# BrushTimer.net
KiCad netlist of a schematic drawn in EAGLE
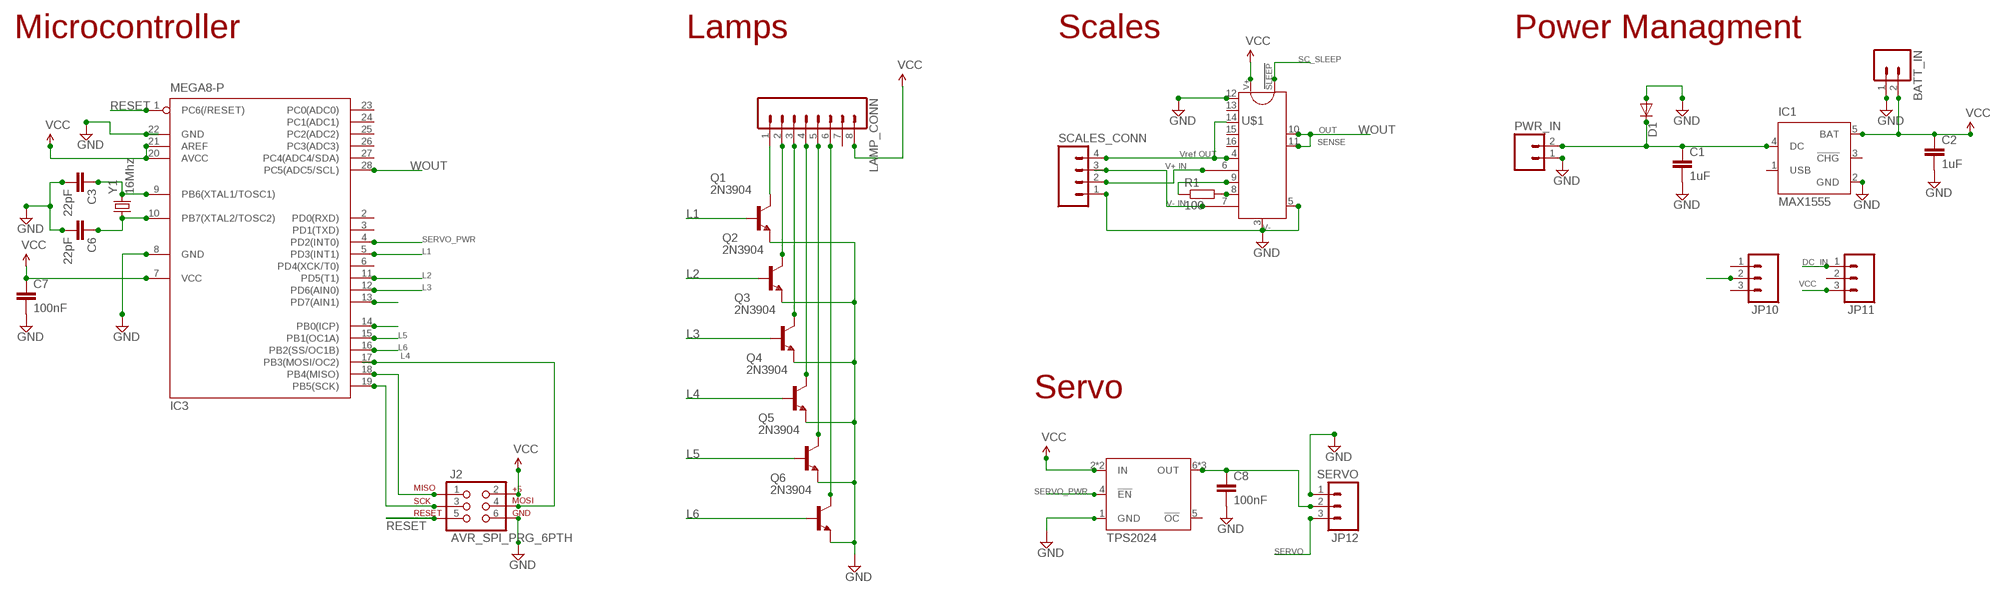
[diagram p0: schematic, sheet 1]

(export (version "E")
  (design (tool "Eeschema 10.0.6"))
  (components
    (comp (ref "BATT_IN")
      (value "M02PTH")
      (footprint "eagle-import:1X02")
      (libsource (lib "eagle-import") (part "M02PTH"))
    )
    (comp (ref "C1")
      (value "1uF")
      (footprint "eagle-import:AXIAL-5MM")
      (libsource (lib "eagle-import") (part "CAP_"))
    )
    (comp (ref "C2")
      (value "1uF")
      (footprint "eagle-import:AXIAL-5MM")
      (libsource (lib "eagle-import") (part "CAP_"))
    )
    (comp (ref "C3")
      (value "22pF")
      (footprint "eagle-import:C2.5-2")
      (libsource (lib "eagle-import") (part "C2.5/2"))
    )
    (comp (ref "C6")
      (value "22pF")
      (footprint "eagle-import:C2.5-2")
      (libsource (lib "eagle-import") (part "C2.5/2"))
    )
    (comp (ref "C7")
      (value "100nF")
      (footprint "eagle-import:C5B3.5")
      (libsource (lib "eagle-import") (part "C5/3.5"))
    )
    (comp (ref "C8")
      (value "100nF")
      (footprint "eagle-import:C5B3.5")
      (libsource (lib "eagle-import") (part "C5/3.5"))
    )
    (comp (ref "D1")
      (value "DIODE-D-2.5")
      (footprint "eagle-import:D-2.5")
      (libsource (lib "eagle-import") (part "DIODE-D-2.5"))
    )
    (comp (ref "IC1")
      (value "MAX1555")
      (footprint "eagle-import:SOT23-5L")
      (fields (field (name "MF") "MAXIM") (field (name "MPN") "MAX1555EZK+T"))
      (libsource (lib "eagle-import") (part "MAX1555"))
    )
    (comp (ref "IC3")
      (value "MEGA8-P")
      (footprint "eagle-import:DIL28-3")
      (libsource (lib "eagle-import") (part "MEGA8-P"))
    )
    (comp (ref "J2")
      (value "AVR_SPI_PRG_6PTH")
      (footprint "eagle-import:2X3")
      (libsource (lib "eagle-import") (part "AVR_SPI_PRG_6PTH"))
    )
    (comp (ref "JP10")
      (value "M03PTH")
      (footprint "eagle-import:1X03")
      (libsource (lib "eagle-import") (part "M03PTH"))
    )
    (comp (ref "JP11")
      (value "M03PTH")
      (footprint "eagle-import:1X03")
      (libsource (lib "eagle-import") (part "M03PTH"))
    )
    (comp (ref "JP12")
      (value "SERVO")
      (footprint "eagle-import:1X03")
      (libsource (lib "eagle-import") (part "M03PTH"))
    )
    (comp (ref "LAMP_CONN")
      (value "M081X08")
      (footprint "eagle-import:1X08")
      (libsource (lib "eagle-import") (part "M081X08"))
    )
    (comp (ref "PWR_IN")
      (value "M02PTH")
      (footprint "eagle-import:1X02")
      (libsource (lib "eagle-import") (part "M02PTH"))
    )
    (comp (ref "Q1")
      (value "2N3904")
      (footprint "eagle-import:TO92")
      (libsource (lib "eagle-import") (part "2N3904"))
    )
    (comp (ref "Q2")
      (value "2N3904")
      (footprint "eagle-import:TO92")
      (libsource (lib "eagle-import") (part "2N3904"))
    )
    (comp (ref "Q3")
      (value "2N3904")
      (footprint "eagle-import:TO92")
      (libsource (lib "eagle-import") (part "2N3904"))
    )
    (comp (ref "Q4")
      (value "2N3904")
      (footprint "eagle-import:TO92")
      (libsource (lib "eagle-import") (part "2N3904"))
    )
    (comp (ref "Q5")
      (value "2N3904")
      (footprint "eagle-import:TO92")
      (libsource (lib "eagle-import") (part "2N3904"))
    )
    (comp (ref "Q6")
      (value "2N3904")
      (footprint "eagle-import:TO92")
      (libsource (lib "eagle-import") (part "2N3904"))
    )
    (comp (ref "R1")
      (value "100")
      (footprint "eagle-import:0207_5V")
      (libsource (lib "eagle-import") (part "R-EU_0207/5V"))
    )
    (comp (ref "SCALES_CONN")
      (value "M04PTH")
      (footprint "eagle-import:1X04")
      (libsource (lib "eagle-import") (part "M04PTH"))
    )
    (comp (ref "U$1")
      (value "INA125")
      (footprint "eagle-import:DIL16")
      (libsource (lib "eagle-import") (part "INA125"))
    )
    (comp (ref "U$2")
      (value "TPS2024")
      (footprint "eagle-import:DIL08-OPTO")
      (libsource (lib "eagle-import") (part "TPS2024"))
    )
    (comp (ref "Y1")
      (value "16Mhz")
      (footprint "eagle-import:HC49US")
      (libsource (lib "eagle-import") (part "CRYSTALHC49US"))
    )
  )
  (nets
    (net (code "1") (name "/DC_IN") (class "Default")
      (node (ref "C1") (pin "P$1") (pinfunction "1_P$1") (pintype "passive"))
      (node (ref "D1") (pin "C") (pinfunction "C_C") (pintype "passive"))
      (node (ref "IC1") (pin "4") (pinfunction "DC_4") (pintype "input"))
      (node (ref "JP11") (pin "1") (pinfunction "1_1") (pintype "passive"))
      (node (ref "PWR_IN") (pin "2") (pinfunction "2_2") (pintype "passive"))
    )
    (net (code "2") (name "/L1") (class "Default")
      (node (ref "IC3") (pin "5") (pinfunction "PD3(INT1)_5") (pintype "bidirectional"))
      (node (ref "Q1") (pin "2") (pinfunction "B_2") (pintype "passive"))
    )
    (net (code "3") (name "/L2") (class "Default")
      (node (ref "IC3") (pin "11") (pinfunction "PD5(T1)_11") (pintype "bidirectional"))
      (node (ref "Q2") (pin "2") (pinfunction "B_2") (pintype "passive"))
    )
    (net (code "4") (name "/L3") (class "Default")
      (node (ref "IC3") (pin "12") (pinfunction "PD6(AIN0)_12") (pintype "bidirectional"))
      (node (ref "Q3") (pin "2") (pinfunction "B_2") (pintype "passive"))
    )
    (net (code "5") (name "/L4") (class "Default")
      (node (ref "IC3") (pin "17") (pinfunction "PB3(MOSI/OC2)_17") (pintype "bidirectional"))
      (node (ref "J2") (pin "4") (pinfunction "4_4") (pintype "passive"))
      (node (ref "Q4") (pin "2") (pinfunction "B_2") (pintype "passive"))
    )
    (net (code "6") (name "/L5") (class "Default")
      (node (ref "IC3") (pin "15") (pinfunction "PB1(OC1A)_15") (pintype "bidirectional"))
      (node (ref "Q5") (pin "2") (pinfunction "B_2") (pintype "passive"))
    )
    (net (code "7") (name "/L6") (class "Default")
      (node (ref "IC3") (pin "16") (pinfunction "PB2(SS/OC1B)_16") (pintype "bidirectional"))
      (node (ref "Q6") (pin "2") (pinfunction "B_2") (pintype "passive"))
    )
    (net (code "8") (name "/RESET") (class "Default")
      (node (ref "IC3") (pin "1") (pinfunction "PC6(/RESET)_1") (pintype "bidirectional"))
      (node (ref "J2") (pin "5") (pinfunction "5_5") (pintype "passive"))
    )
    (net (code "9") (name "/SC_SLEEP") (class "Default")
      (node (ref "IC3") (pin "13") (pinfunction "PD7(AIN1)_13") (pintype "bidirectional"))
      (node (ref "U$1") (pin "2") (pinfunction "2_2") (pintype "power_in"))
    )
    (net (code "10") (name "/SERVO") (class "Default")
      (node (ref "IC3") (pin "14") (pinfunction "PB0(ICP)_14") (pintype "bidirectional"))
      (node (ref "JP12") (pin "3") (pinfunction "3_3") (pintype "passive"))
    )
    (net (code "11") (name "/SERVO_PWR") (class "Default")
      (node (ref "IC3") (pin "4") (pinfunction "PD2(INT0)_4") (pintype "bidirectional"))
      (node (ref "U$2") (pin "4") (pinfunction "~{EN}_4") (pintype "input"))
    )
    (net (code "12") (name "/WOUT") (class "Default")
      (node (ref "IC3") (pin "28") (pinfunction "PC5(ADC5/SCL)_28") (pintype "bidirectional"))
      (node (ref "U$1") (pin "10") (pinfunction "10_10") (pintype "output"))
      (node (ref "U$1") (pin "11") (pinfunction "11_11") (pintype "output"))
    )
    (net (code "13") (name "GND") (class "Default")
      (node (ref "BATT_IN") (pin "1") (pinfunction "1_1") (pintype "passive"))
      (node (ref "C1") (pin "P$2") (pinfunction "2_P$2") (pintype "passive"))
      (node (ref "C2") (pin "P$2") (pinfunction "2_P$2") (pintype "passive"))
      (node (ref "C3") (pin "2") (pinfunction "2_2") (pintype "passive"))
      (node (ref "C6") (pin "2") (pinfunction "2_2") (pintype "passive"))
      (node (ref "C7") (pin "2") (pinfunction "2_2") (pintype "passive"))
      (node (ref "C8") (pin "2") (pinfunction "2_2") (pintype "passive"))
      (node (ref "D1") (pin "A") (pinfunction "A_A") (pintype "passive"))
      (node (ref "IC1") (pin "2") (pinfunction "GND_2") (pintype "power_in"))
      (node (ref "IC3") (pin "22") (pinfunction "GND_22") (pintype "power_in"))
      (node (ref "IC3") (pin "8") (pinfunction "GND_8") (pintype "power_in"))
      (node (ref "J2") (pin "6") (pinfunction "6_6") (pintype "passive"))
      (node (ref "JP10") (pin "2") (pinfunction "2_2") (pintype "passive"))
      (node (ref "JP12") (pin "1") (pinfunction "1_1") (pintype "passive"))
      (node (ref "PWR_IN") (pin "1") (pinfunction "1_1") (pintype "passive"))
      (node (ref "Q1") (pin "3") (pinfunction "E_3") (pintype "passive"))
      (node (ref "Q2") (pin "3") (pinfunction "E_3") (pintype "passive"))
      (node (ref "Q3") (pin "3") (pinfunction "E_3") (pintype "passive"))
      (node (ref "Q4") (pin "3") (pinfunction "E_3") (pintype "passive"))
      (node (ref "Q5") (pin "3") (pinfunction "E_3") (pintype "passive"))
      (node (ref "Q6") (pin "3") (pinfunction "E_3") (pintype "passive"))
      (node (ref "SCALES_CONN") (pin "1") (pinfunction "1_1") (pintype "passive"))
      (node (ref "U$1") (pin "12") (pinfunction "12_12") (pintype "input"))
      (node (ref "U$1") (pin "3") (pinfunction "3_3") (pintype "passive"))
      (node (ref "U$1") (pin "5") (pinfunction "5_5") (pintype "passive"))
      (node (ref "U$2") (pin "1") (pinfunction "GND_1") (pintype "power_in"))
    )
    (net (code "14") (name "Net-(C8-Pad1)") (class "Default")
      (node (ref "C8") (pin "1") (pinfunction "1_1") (pintype "passive"))
      (node (ref "JP12") (pin "2") (pinfunction "2_2") (pintype "passive"))
      (node (ref "U$2") (pin "6") (pinfunction "OUT_6") (pintype "output"))
      (node (ref "U$2") (pin "7") (pinfunction "OUT_7") (pintype "output"))
      (node (ref "U$2") (pin "8") (pinfunction "OUT_8") (pintype "output"))
    )
    (net (code "15") (name "Net-(IC3-PB4(MISO))") (class "Default")
      (node (ref "IC3") (pin "18") (pinfunction "PB4(MISO)_18") (pintype "bidirectional"))
      (node (ref "J2") (pin "1") (pinfunction "1_1") (pintype "passive"))
    )
    (net (code "16") (name "Net-(IC3-PB5(SCK))") (class "Default")
      (node (ref "IC3") (pin "19") (pinfunction "PB5(SCK)_19") (pintype "bidirectional"))
      (node (ref "J2") (pin "3") (pinfunction "3_3") (pintype "passive"))
    )
    (net (code "17") (name "Net-(IC3-PB6(XTAL1{slash}TOSC1))") (class "Default")
      (node (ref "C3") (pin "1") (pinfunction "1_1") (pintype "passive"))
      (node (ref "IC3") (pin "9") (pinfunction "PB6(XTAL1/TOSC1)_9") (pintype "bidirectional"))
      (node (ref "Y1") (pin "2") (pinfunction "2_2") (pintype "passive"))
    )
    (net (code "18") (name "Net-(IC3-PB7(XTAL2{slash}TOSC2))") (class "Default")
      (node (ref "C6") (pin "1") (pinfunction "1_1") (pintype "passive"))
      (node (ref "IC3") (pin "10") (pinfunction "PB7(XTAL2/TOSC2)_10") (pintype "bidirectional"))
      (node (ref "Y1") (pin "1") (pinfunction "1_1") (pintype "passive"))
    )
    (net (code "19") (name "Net-(Q1-C)") (class "Default")
      (node (ref "LAMP_CONN") (pin "1") (pinfunction "1_1") (pintype "passive"))
      (node (ref "Q1") (pin "1") (pinfunction "C_1") (pintype "passive"))
    )
    (net (code "20") (name "Net-(Q2-C)") (class "Default")
      (node (ref "LAMP_CONN") (pin "2") (pinfunction "2_2") (pintype "passive"))
      (node (ref "Q2") (pin "1") (pinfunction "C_1") (pintype "passive"))
    )
    (net (code "21") (name "Net-(Q3-C)") (class "Default")
      (node (ref "LAMP_CONN") (pin "3") (pinfunction "3_3") (pintype "passive"))
      (node (ref "Q3") (pin "1") (pinfunction "C_1") (pintype "passive"))
    )
    (net (code "22") (name "Net-(Q4-C)") (class "Default")
      (node (ref "LAMP_CONN") (pin "4") (pinfunction "4_4") (pintype "passive"))
      (node (ref "Q4") (pin "1") (pinfunction "C_1") (pintype "passive"))
    )
    (net (code "23") (name "Net-(Q5-C)") (class "Default")
      (node (ref "LAMP_CONN") (pin "5") (pinfunction "5_5") (pintype "passive"))
      (node (ref "Q5") (pin "1") (pinfunction "C_1") (pintype "passive"))
    )
    (net (code "24") (name "Net-(Q6-C)") (class "Default")
      (node (ref "LAMP_CONN") (pin "6") (pinfunction "6_6") (pintype "passive"))
      (node (ref "Q6") (pin "1") (pinfunction "C_1") (pintype "passive"))
    )
    (net (code "25") (name "Net-(R1-Pad1)") (class "Default")
      (node (ref "R1") (pin "1") (pinfunction "1_1") (pintype "passive"))
      (node (ref "U$1") (pin "9") (pinfunction "9_9") (pintype "passive"))
    )
    (net (code "26") (name "Net-(R1-Pad2)") (class "Default")
      (node (ref "R1") (pin "2") (pinfunction "2_2") (pintype "passive"))
      (node (ref "U$1") (pin "8") (pinfunction "8_8") (pintype "passive"))
    )
    (net (code "27") (name "Net-(SCALES_CONN-Pad2)") (class "Default")
      (node (ref "SCALES_CONN") (pin "2") (pinfunction "2_2") (pintype "passive"))
      (node (ref "U$1") (pin "6") (pinfunction "6_6") (pintype "input"))
    )
    (net (code "28") (name "Net-(SCALES_CONN-Pad3)") (class "Default")
      (node (ref "SCALES_CONN") (pin "3") (pinfunction "3_3") (pintype "passive"))
      (node (ref "U$1") (pin "7") (pinfunction "7_7") (pintype "passive"))
    )
    (net (code "29") (name "Net-(SCALES_CONN-Pad4)") (class "Default")
      (node (ref "SCALES_CONN") (pin "4") (pinfunction "4_4") (pintype "passive"))
      (node (ref "U$1") (pin "14") (pinfunction "14_14") (pintype "input"))
      (node (ref "U$1") (pin "4") (pinfunction "4_4") (pintype "input"))
    )
    (net (code "30") (name "VCC") (class "Default")
      (node (ref "BATT_IN") (pin "2") (pinfunction "2_2") (pintype "passive"))
      (node (ref "C2") (pin "P$1") (pinfunction "1_P$1") (pintype "passive"))
      (node (ref "C7") (pin "1") (pinfunction "1_1") (pintype "passive"))
      (node (ref "IC1") (pin "5") (pinfunction "BAT_5") (pintype "passive"))
      (node (ref "IC3") (pin "20") (pinfunction "AVCC_20") (pintype "power_in"))
      (node (ref "IC3") (pin "21") (pinfunction "AREF_21") (pintype "passive"))
      (node (ref "IC3") (pin "7") (pinfunction "VCC_7") (pintype "power_in"))
      (node (ref "J2") (pin "2") (pinfunction "2_2") (pintype "passive"))
      (node (ref "JP11") (pin "3") (pinfunction "3_3") (pintype "passive"))
      (node (ref "LAMP_CONN") (pin "8") (pinfunction "8_8") (pintype "passive"))
      (node (ref "U$1") (pin "1") (pinfunction "1_1") (pintype "power_in"))
      (node (ref "U$2") (pin "2") (pinfunction "IN_2") (pintype "input"))
      (node (ref "U$2") (pin "3") (pinfunction "IN_3") (pintype "input"))
    )
    (net (code "31") (name "unconnected-(IC1-USB-Pad1)") (class "Default")
      (node (ref "IC1") (pin "1") (pinfunction "USB_1") (pintype "input"))
    )
    (net (code "32") (name "unconnected-(IC1-~{CHG}-Pad3)") (class "Default")
      (node (ref "IC1") (pin "3") (pinfunction "~{CHG}_3") (pintype "output"))
    )
    (net (code "33") (name "unconnected-(IC3-PC0(ADC0)-Pad23)") (class "Default")
      (node (ref "IC3") (pin "23") (pinfunction "PC0(ADC0)_23") (pintype "bidirectional"))
    )
    (net (code "34") (name "unconnected-(IC3-PC1(ADC1)-Pad24)") (class "Default")
      (node (ref "IC3") (pin "24") (pinfunction "PC1(ADC1)_24") (pintype "bidirectional"))
    )
    (net (code "35") (name "unconnected-(IC3-PC2(ADC2)-Pad25)") (class "Default")
      (node (ref "IC3") (pin "25") (pinfunction "PC2(ADC2)_25") (pintype "bidirectional"))
    )
    (net (code "36") (name "unconnected-(IC3-PC3(ADC3)-Pad26)") (class "Default")
      (node (ref "IC3") (pin "26") (pinfunction "PC3(ADC3)_26") (pintype "bidirectional"))
    )
    (net (code "37") (name "unconnected-(IC3-PC4(ADC4{slash}SDA)-Pad27)") (class "Default")
      (node (ref "IC3") (pin "27") (pinfunction "PC4(ADC4/SDA)_27") (pintype "bidirectional"))
    )
    (net (code "38") (name "unconnected-(IC3-PD0(RXD)-Pad2)") (class "Default")
      (node (ref "IC3") (pin "2") (pinfunction "PD0(RXD)_2") (pintype "bidirectional"))
    )
    (net (code "39") (name "unconnected-(IC3-PD1(TXD)-Pad3)") (class "Default")
      (node (ref "IC3") (pin "3") (pinfunction "PD1(TXD)_3") (pintype "bidirectional"))
    )
    (net (code "40") (name "unconnected-(IC3-PD4(XCK{slash}T0)-Pad6)") (class "Default")
      (node (ref "IC3") (pin "6") (pinfunction "PD4(XCK/T0)_6") (pintype "bidirectional"))
    )
    (net (code "41") (name "unconnected-(JP10-Pad1)") (class "Default")
      (node (ref "JP10") (pin "1") (pinfunction "1_1") (pintype "passive"))
    )
    (net (code "42") (name "unconnected-(JP10-Pad3)") (class "Default")
      (node (ref "JP10") (pin "3") (pinfunction "3_3") (pintype "passive"))
    )
    (net (code "43") (name "unconnected-(JP11-Pad2)") (class "Default")
      (node (ref "JP11") (pin "2") (pinfunction "2_2") (pintype "passive"))
    )
    (net (code "44") (name "unconnected-(LAMP_CONN-Pad7)") (class "Default")
      (node (ref "LAMP_CONN") (pin "7") (pinfunction "7_7") (pintype "passive"))
    )
    (net (code "45") (name "unconnected-(U$1-Pad13)") (class "Default")
      (node (ref "U$1") (pin "13") (pinfunction "13_13") (pintype "input"))
    )
    (net (code "46") (name "unconnected-(U$1-Pad15)") (class "Default")
      (node (ref "U$1") (pin "15") (pinfunction "15_15") (pintype "input"))
    )
    (net (code "47") (name "unconnected-(U$1-Pad16)") (class "Default")
      (node (ref "U$1") (pin "16") (pinfunction "16_16") (pintype "input"))
    )
    (net (code "48") (name "unconnected-(U$2-~{OC}-Pad5)") (class "Default")
      (node (ref "U$2") (pin "5") (pinfunction "~{OC}_5") (pintype "open_collector"))
    )
  )
)
